# Sheet2.net
KiCad netlist of a schematic drawn in Altium Designer
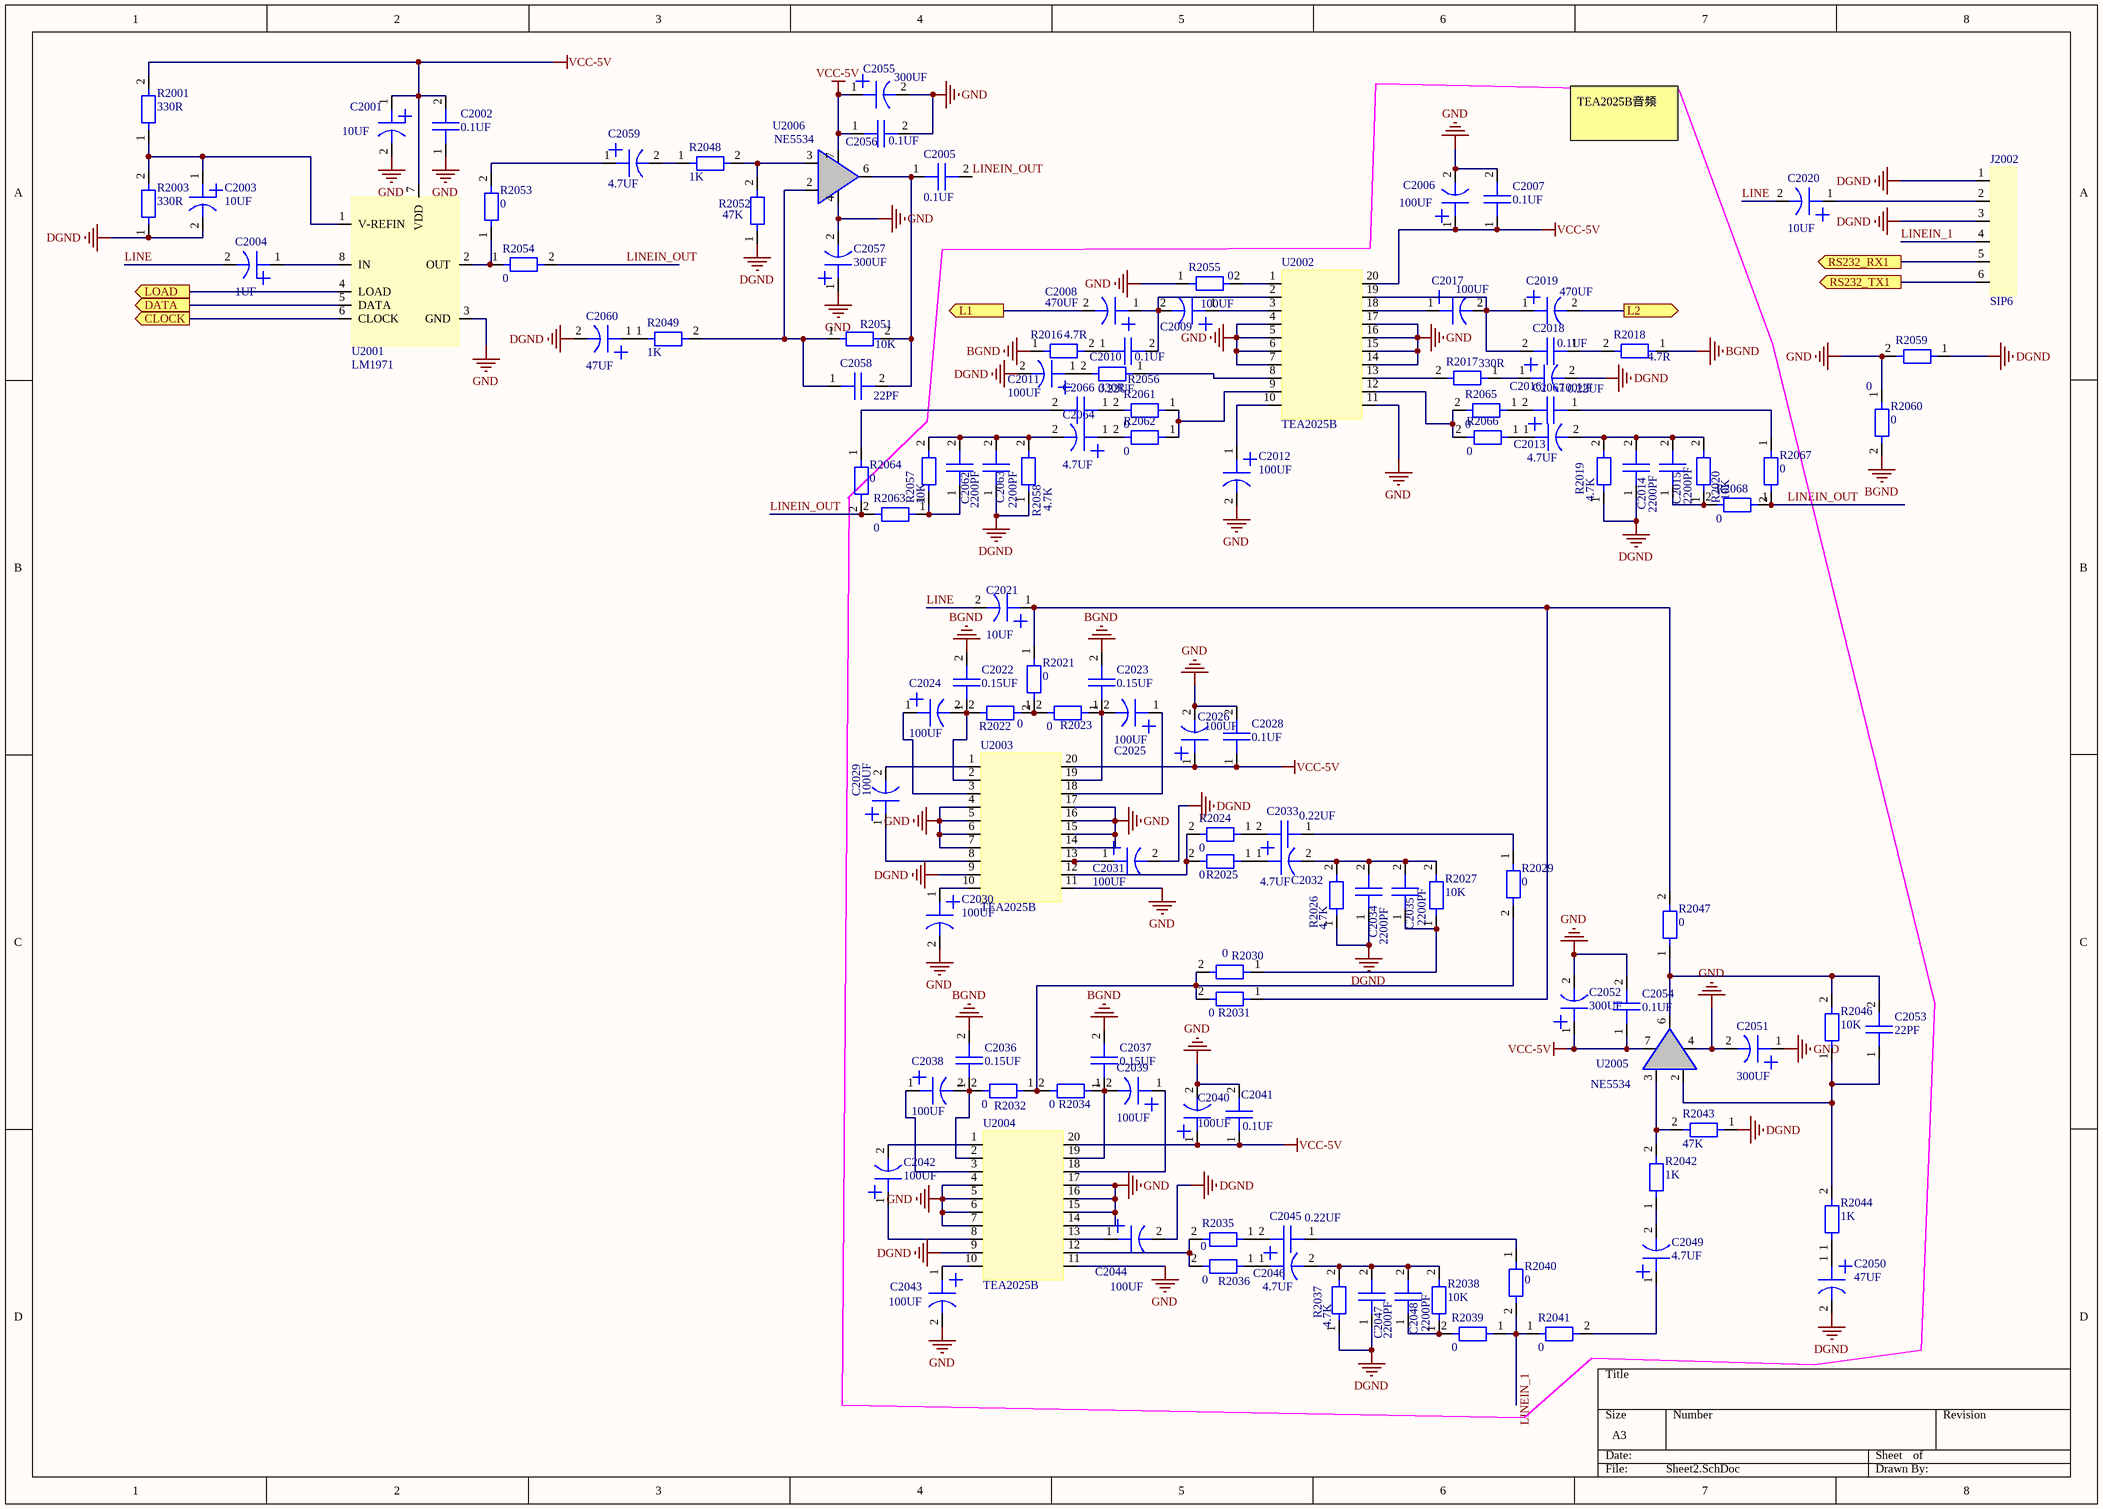
[diagram p0: Sheet2.SchDoc]

(export (version "E")
  (design (tool "Eeschema 10.0.6"))
  (components
    (comp (ref "C2001") (value "10UF") (footprint "7343") (libsource (lib "Schlib1") (part "EC")))
    (comp (ref "C2002") (value "0.1UF") (footprint "0603") (libsource (lib "Schlib1") (part "C")))
    (comp (ref "C2003") (value "10UF") (footprint "7343") (libsource (lib "Schlib1") (part "EC")))
    (comp (ref "C2004") (value "1UF") (footprint "7343") (libsource (lib "Schlib1") (part "EC")))
    (comp (ref "C2005") (value "0.1UF") (footprint "0603") (libsource (lib "Schlib1") (part "C")))
    (comp (ref "C2006") (value "100UF") (footprint "7343") (libsource (lib "Schlib1") (part "JC")))
    (comp (ref "C2007") (value "0.1UF") (footprint "0603") (libsource (lib "Schlib1") (part "C")))
    (comp (ref "C2008") (value "470UF") (footprint "7343") (libsource (lib "Schlib1") (part "JC")))
    (comp (ref "C2009") (value "100UF") (footprint "7343") (libsource (lib "Schlib1") (part "JC")))
    (comp (ref "C2010") (value "0.1UF") (footprint "0603") (libsource (lib "Schlib1") (part "C")))
    (comp (ref "C2011") (value "100UF") (footprint "7343") (libsource (lib "Schlib1") (part "JC")))
    (comp (ref "C2012") (value "100UF") (footprint "7343") (libsource (lib "Schlib1") (part "JC")))
    (comp (ref "C2013") (value "4.7UF") (footprint "7343") (libsource (lib "Schlib1") (part "JC")))
    (comp (ref "C2014") (value "2200PF") (footprint "0603") (libsource (lib "Schlib1") (part "C")))
    (comp (ref "C2015") (value "2200PF") (footprint "0603") (libsource (lib "Schlib1") (part "C")))
    (comp (ref "C2016") (value "100UF") (footprint "7343") (libsource (lib "Schlib1") (part "JC")))
    (comp (ref "C2017") (value "100UF") (footprint "7343") (libsource (lib "Schlib1") (part "JC")))
    (comp (ref "C2018") (value "0.1UF") (footprint "0603") (libsource (lib "Schlib1") (part "C")))
    (comp (ref "C2019") (value "470UF") (footprint "7343") (libsource (lib "Schlib1") (part "JC")))
    (comp (ref "C2020") (value "10UF") (footprint "7343") (libsource (lib "Schlib1") (part "JC")))
    (comp (ref "C2021") (value "10UF") (footprint "7343") (libsource (lib "Schlib1") (part "JC")))
    (comp (ref "C2022") (value "0.15UF") (footprint "0603") (libsource (lib "Schlib1") (part "C")))
    (comp (ref "C2023") (value "0.15UF") (footprint "0603") (libsource (lib "Schlib1") (part "C")))
    (comp (ref "C2024") (value "100UF") (footprint "7343") (libsource (lib "Schlib1") (part "JC")))
    (comp (ref "C2025") (value "100UF") (footprint "7343") (libsource (lib "Schlib1") (part "JC")))
    (comp (ref "C2026") (value "100UF") (footprint "7343") (libsource (lib "Schlib1") (part "JC")))
    (comp (ref "C2028") (value "0.1UF") (footprint "0603") (libsource (lib "Schlib1") (part "C")))
    (comp (ref "C2029") (value "100UF") (footprint "7343") (libsource (lib "Schlib1") (part "JC")))
    (comp (ref "C2030") (value "100UF") (footprint "7343") (libsource (lib "Schlib1") (part "JC")))
    (comp (ref "C2031") (value "100UF") (footprint "7343") (libsource (lib "Schlib1") (part "JC")))
    (comp (ref "C2032") (value "4.7UF") (footprint "7343") (libsource (lib "Schlib1") (part "JC")))
    (comp (ref "C2033") (value "0.22UF") (footprint "0603") (libsource (lib "Schlib1") (part "C")))
    (comp (ref "C2034") (value "2200PF") (footprint "0603") (libsource (lib "Schlib1") (part "C")))
    (comp (ref "C2035") (value "2200PF") (footprint "0603") (libsource (lib "Schlib1") (part "C")))
    (comp (ref "C2036") (value "0.15UF") (footprint "0603") (libsource (lib "Schlib1") (part "C")))
    (comp (ref "C2037") (value "0.15UF") (footprint "0603") (libsource (lib "Schlib1") (part "C")))
    (comp (ref "C2038") (value "100UF") (footprint "7343") (libsource (lib "Schlib1") (part "JC")))
    (comp (ref "C2039") (value "100UF") (footprint "7343") (libsource (lib "Schlib1") (part "JC")))
    (comp (ref "C2040") (value "100UF") (footprint "7343") (libsource (lib "Schlib1") (part "JC")))
    (comp (ref "C2041") (value "0.1UF") (footprint "0603") (libsource (lib "Schlib1") (part "C")))
    (comp (ref "C2042") (value "100UF") (footprint "7343") (libsource (lib "Schlib1") (part "JC")))
    (comp (ref "C2043") (value "100UF") (footprint "7343") (libsource (lib "Schlib1") (part "JC")))
    (comp (ref "C2044") (value "100UF") (footprint "7343") (libsource (lib "Schlib1") (part "JC")))
    (comp (ref "C2045") (value "0.22UF") (footprint "0603") (libsource (lib "Schlib1") (part "C")))
    (comp (ref "C2046") (value "4.7UF") (footprint "7343") (libsource (lib "Schlib1") (part "JC")))
    (comp (ref "C2047") (value "2200PF") (footprint "0603") (libsource (lib "Schlib1") (part "C")))
    (comp (ref "C2048") (value "2200PF") (footprint "0603") (libsource (lib "Schlib1") (part "C")))
    (comp (ref "C2049") (value "4.7UF") (footprint "7343") (libsource (lib "Schlib1") (part "JC")))
    (comp (ref "C2050") (value "47UF") (footprint "7343") (libsource (lib "Schlib1") (part "JC")))
    (comp (ref "C2051") (value "300UF") (footprint "7343") (libsource (lib "Schlib1") (part "JC")))
    (comp (ref "C2052") (value "300UF") (footprint "7343") (libsource (lib "Schlib1") (part "JC")))
    (comp (ref "C2053") (value "22PF") (footprint "0603") (libsource (lib "Schlib1") (part "C")))
    (comp (ref "C2054") (value "0.1UF") (footprint "0603") (libsource (lib "Schlib1") (part "C")))
    (comp (ref "C2055") (value "300UF") (footprint "7343") (libsource (lib "Schlib1") (part "JC")))
    (comp (ref "C2056") (value "0.1UF") (footprint "0603") (libsource (lib "Schlib1") (part "C")))
    (comp (ref "C2057") (value "300UF") (footprint "7343") (libsource (lib "Schlib1") (part "JC")))
    (comp (ref "C2058") (value "22PF") (footprint "0603") (libsource (lib "Schlib1") (part "C")))
    (comp (ref "C2059") (value "4.7UF") (footprint "7343") (libsource (lib "Schlib1") (part "JC")))
    (comp (ref "C2060") (value "47UF") (footprint "7343") (libsource (lib "Schlib1") (part "JC")))
    (comp (ref "C2062") (value "2200PF") (footprint "0603") (libsource (lib "Schlib1") (part "C")))
    (comp (ref "C2063") (value "2200PF") (footprint "0603") (libsource (lib "Schlib1") (part "C")))
    (comp (ref "C2064") (value "4.7UF") (footprint "7343") (libsource (lib "Schlib1") (part "JC")))
    (comp (ref "C2066") (value "0.22UF") (footprint "0603") (libsource (lib "Schlib1") (part "C")))
    (comp (ref "C2067") (value "0.22UF") (footprint "0603") (libsource (lib "Schlib1") (part "C")))
    (comp (ref "J2002") (value "SIP6") (footprint "SIP6") (libsource (lib "Schlib1") (part "SIP6")))
    (comp (ref "R2001") (value "330R") (footprint "0603") (libsource (lib "Schlib1") (part "R")))
    (comp (ref "R2003") (value "330R") (footprint "0603") (libsource (lib "Schlib1") (part "R")))
    (comp (ref "R2016") (value "4.7R") (footprint "0603") (libsource (lib "Schlib1") (part "R")))
    (comp (ref "R2017") (value "330R") (footprint "0603") (libsource (lib "Schlib1") (part "R")))
    (comp (ref "R2018") (value "4.7R") (footprint "0603") (libsource (lib "Schlib1") (part "R")))
    (comp (ref "R2019") (value "4.7K") (footprint "0603") (libsource (lib "Schlib1") (part "R")))
    (comp (ref "R2020") (value "10K") (footprint "0603") (libsource (lib "Schlib1") (part "R")))
    (comp (ref "R2021") (value "0") (footprint "0603") (libsource (lib "Schlib1") (part "R")))
    (comp (ref "R2022") (value "0") (footprint "0603") (libsource (lib "Schlib1") (part "R")))
    (comp (ref "R2023") (value "0") (footprint "0603") (libsource (lib "Schlib1") (part "R")))
    (comp (ref "R2024") (value "0") (footprint "0603") (libsource (lib "Schlib1") (part "R")))
    (comp (ref "R2025") (value "0") (footprint "0603") (libsource (lib "Schlib1") (part "R")))
    (comp (ref "R2026") (value "4.7K") (footprint "0603") (libsource (lib "Schlib1") (part "R")))
    (comp (ref "R2027") (value "10K") (footprint "0603") (libsource (lib "Schlib1") (part "R")))
    (comp (ref "R2029") (value "0") (footprint "0603") (libsource (lib "Schlib1") (part "R")))
    (comp (ref "R2030") (value "0") (footprint "0603") (libsource (lib "Schlib1") (part "R")))
    (comp (ref "R2031") (value "0") (footprint "0603") (libsource (lib "Schlib1") (part "R")))
    (comp (ref "R2032") (value "0") (footprint "0603") (libsource (lib "Schlib1") (part "R")))
    (comp (ref "R2034") (value "0") (footprint "0603") (libsource (lib "Schlib1") (part "R")))
    (comp (ref "R2035") (value "0") (footprint "0603") (libsource (lib "Schlib1") (part "R")))
    (comp (ref "R2036") (value "0") (footprint "0603") (libsource (lib "Schlib1") (part "R")))
    (comp (ref "R2037") (value "4.7K") (footprint "0603") (libsource (lib "Schlib1") (part "R")))
    (comp (ref "R2038") (value "10K") (footprint "0603") (libsource (lib "Schlib1") (part "R")))
    (comp (ref "R2039") (value "0") (footprint "0603") (libsource (lib "Schlib1") (part "R")))
    (comp (ref "R2040") (value "0") (footprint "0603") (libsource (lib "Schlib1") (part "R")))
    (comp (ref "R2041") (value "0") (footprint "0603") (libsource (lib "Schlib1") (part "R")))
    (comp (ref "R2042") (value "1K") (footprint "0603") (libsource (lib "Schlib1") (part "R")))
    (comp (ref "R2043") (value "47K") (footprint "0603") (libsource (lib "Schlib1") (part "R")))
    (comp (ref "R2044") (value "1K") (footprint "0603") (libsource (lib "Schlib1") (part "R")))
    (comp (ref "R2046") (value "10K") (footprint "0603") (libsource (lib "Schlib1") (part "R")))
    (comp (ref "R2047") (value "0") (footprint "0603") (libsource (lib "Schlib1") (part "R")))
    (comp (ref "R2048") (value "1K") (footprint "0603") (libsource (lib "Schlib1") (part "R")))
    (comp (ref "R2049") (value "1K") (footprint "0603") (libsource (lib "Schlib1") (part "R")))
    (comp (ref "R2051") (value "10K") (footprint "0603") (libsource (lib "Schlib1") (part "R")))
    (comp (ref "R2052") (value "47K") (footprint "0603") (libsource (lib "Schlib1") (part "R")))
    (comp (ref "R2053") (value "0") (footprint "0603") (libsource (lib "Schlib1") (part "R")))
    (comp (ref "R2054") (value "0") (footprint "0603") (libsource (lib "Schlib1") (part "R")))
    (comp (ref "R2055") (value "0") (footprint "0603") (libsource (lib "Schlib1") (part "R")))
    (comp (ref "R2056") (value "330R") (footprint "0603") (libsource (lib "Schlib1") (part "R")))
    (comp (ref "R2057") (value "10K") (footprint "0603") (libsource (lib "Schlib1") (part "R")))
    (comp (ref "R2058") (value "4.7K") (footprint "0603") (libsource (lib "Schlib1") (part "R")))
    (comp (ref "R2059") (value "0") (footprint "0603") (libsource (lib "Schlib1") (part "R")))
    (comp (ref "R2060") (value "0") (footprint "0603") (libsource (lib "Schlib1") (part "R")))
    (comp (ref "R2061") (value "0") (footprint "0603") (libsource (lib "Schlib1") (part "R")))
    (comp (ref "R2062") (value "0") (footprint "0603") (libsource (lib "Schlib1") (part "R")))
    (comp (ref "R2063") (value "0") (footprint "0603") (libsource (lib "Schlib1") (part "R")))
    (comp (ref "R2064") (value "0") (footprint "0603") (libsource (lib "Schlib1") (part "R")))
    (comp (ref "R2065") (value "0") (footprint "0603") (libsource (lib "Schlib1") (part "R")))
    (comp (ref "R2066") (value "0") (footprint "0603") (libsource (lib "Schlib1") (part "R")))
    (comp (ref "R2067") (value "0") (footprint "0603") (libsource (lib "Schlib1") (part "R")))
    (comp (ref "R2068") (value "0") (footprint "0603") (libsource (lib "Schlib1") (part "R")))
    (comp (ref "U2001") (value "LM1971") (footprint "TJA1040") (libsource (lib "Schlib1") (part "LM1971")))
    (comp (ref "U2002")
      (value "TEA2025B")
      (footprint "TEA2025B")
      (libsource (lib "Schlib1") (part "TEA2025B"))
    )
    (comp (ref "U2003")
      (value "TEA2025B")
      (footprint "TEA2025B")
      (libsource (lib "Schlib1") (part "TEA2025B"))
    )
    (comp (ref "U2004")
      (value "TEA2025B")
      (footprint "TEA2025B")
      (libsource (lib "Schlib1") (part "TEA2025B"))
    )
    (comp (ref "U2005") (value "NE5534") (footprint "SP2526A") (libsource (lib "Schlib1") (part "NE5534")))
    (comp (ref "U2006") (value "NE5534") (footprint "SP2526A") (libsource (lib "Schlib1") (part "NE5534")))
  )
  (nets
    (net (code "1") (name "/CLOCK") (class "Default")
      (node (ref "U2001") (pin "6") (pinfunction "CLOCK_6") (pintype "passive"))
    )
    (net (code "2") (name "/DATA") (class "Default")
      (node (ref "U2001") (pin "5") (pinfunction "DATA_5") (pintype "passive"))
    )
    (net (code "3") (name "/L1") (class "Default") (node (ref "C2008") (pin "2") (pintype "passive")))
    (net (code "4") (name "/L2") (class "Default") (node (ref "C2019") (pin "2") (pintype "passive")))
    (net (code "5") (name "/LINE") (class "Default")
      (node (ref "C2004") (pin "2") (pintype "passive"))
      (node (ref "C2020") (pin "2") (pintype "passive"))
      (node (ref "C2021") (pin "2") (pintype "passive"))
    )
    (net (code "6") (name "/LINEIN_1") (class "Default")
      (node (ref "J2002") (pin "4") (pintype "passive"))
      (node (ref "R2039") (pin "1") (pintype "passive"))
      (node (ref "R2040") (pin "2") (pintype "passive"))
      (node (ref "R2041") (pin "1") (pintype "passive"))
    )
    (net (code "7") (name "/LINEIN_OUT") (class "Default")
      (node (ref "C2005") (pin "2") (pintype "passive"))
      (node (ref "R2054") (pin "2") (pintype "passive"))
      (node (ref "R2063") (pin "2") (pintype "passive"))
      (node (ref "R2064") (pin "2") (pintype "passive"))
      (node (ref "R2067") (pin "2") (pintype "passive"))
      (node (ref "R2068") (pin "1") (pintype "passive"))
    )
    (net (code "8") (name "/LOAD") (class "Default")
      (node (ref "U2001") (pin "4") (pinfunction "LOAD_4") (pintype "passive"))
    )
    (net (code "9") (name "/RS232_RX1") (class "Default") (node (ref "J2002") (pin "5") (pintype "passive")))
    (net (code "10") (name "/RS232_TX1") (class "Default") (node (ref "J2002") (pin "6") (pintype "passive")))
    (net (code "11") (name "BGND") (class "Default")
      (node (ref "C2022") (pin "2") (pintype "passive"))
      (node (ref "C2023") (pin "2") (pintype "passive"))
      (node (ref "C2036") (pin "2") (pintype "passive"))
      (node (ref "C2037") (pin "2") (pintype "passive"))
      (node (ref "R2016") (pin "1") (pintype "passive"))
      (node (ref "R2018") (pin "1") (pintype "passive"))
      (node (ref "R2060") (pin "2") (pintype "passive"))
    )
    (net (code "12") (name "DGND") (class "Default")
      (node (ref "C2003") (pin "2") (pintype "passive"))
      (node (ref "C2011") (pin "2") (pintype "passive"))
      (node (ref "C2014") (pin "1") (pintype "passive"))
      (node (ref "C2016") (pin "2") (pintype "passive"))
      (node (ref "C2031") (pin "2") (pintype "passive"))
      (node (ref "C2034") (pin "1") (pintype "passive"))
      (node (ref "C2044") (pin "2") (pintype "passive"))
      (node (ref "C2047") (pin "1") (pintype "passive"))
      (node (ref "C2050") (pin "2") (pintype "passive"))
      (node (ref "C2060") (pin "2") (pintype "passive"))
      (node (ref "C2063") (pin "1") (pintype "passive"))
      (node (ref "J2002") (pin "1") (pintype "passive"))
      (node (ref "J2002") (pin "3") (pintype "passive"))
      (node (ref "R2003") (pin "1") (pintype "passive"))
      (node (ref "R2019") (pin "1") (pintype "passive"))
      (node (ref "R2026") (pin "1") (pintype "passive"))
      (node (ref "R2037") (pin "1") (pintype "passive"))
      (node (ref "R2043") (pin "1") (pintype "passive"))
      (node (ref "R2052") (pin "1") (pintype "passive"))
      (node (ref "R2058") (pin "1") (pintype "passive"))
      (node (ref "R2059") (pin "1") (pintype "passive"))
      (node (ref "U2003") (pin "9") (pintype "passive"))
      (node (ref "U2004") (pin "9") (pintype "passive"))
    )
    (net (code "13") (name "GND") (class "Default")
      (node (ref "C2001") (pin "2") (pintype "passive"))
      (node (ref "C2002") (pin "1") (pintype "passive"))
      (node (ref "C2006") (pin "2") (pintype "passive"))
      (node (ref "C2007") (pin "2") (pintype "passive"))
      (node (ref "C2012") (pin "2") (pintype "passive"))
      (node (ref "C2026") (pin "2") (pintype "passive"))
      (node (ref "C2028") (pin "2") (pintype "passive"))
      (node (ref "C2030") (pin "2") (pintype "passive"))
      (node (ref "C2040") (pin "2") (pintype "passive"))
      (node (ref "C2041") (pin "2") (pintype "passive"))
      (node (ref "C2043") (pin "2") (pintype "passive"))
      (node (ref "C2051") (pin "1") (pintype "passive"))
      (node (ref "C2051") (pin "2") (pintype "passive"))
      (node (ref "C2052") (pin "2") (pintype "passive"))
      (node (ref "C2054") (pin "2") (pintype "passive"))
      (node (ref "C2055") (pin "2") (pintype "passive"))
      (node (ref "C2056") (pin "2") (pintype "passive"))
      (node (ref "C2057") (pin "1") (pintype "passive"))
      (node (ref "C2057") (pin "2") (pintype "passive"))
      (node (ref "R2055") (pin "1") (pintype "passive"))
      (node (ref "R2059") (pin "2") (pintype "passive"))
      (node (ref "R2060") (pin "1") (pintype "passive"))
      (node (ref "U2001") (pin "3") (pinfunction "GND_3") (pintype "passive"))
      (node (ref "U2002") (pin "11") (pintype "passive"))
      (node (ref "U2002") (pin "14") (pintype "passive"))
      (node (ref "U2002") (pin "15") (pintype "passive"))
      (node (ref "U2002") (pin "16") (pintype "passive"))
      (node (ref "U2002") (pin "17") (pintype "passive"))
      (node (ref "U2002") (pin "4") (pintype "passive"))
      (node (ref "U2002") (pin "5") (pintype "passive"))
      (node (ref "U2002") (pin "6") (pintype "passive"))
      (node (ref "U2002") (pin "7") (pintype "passive"))
      (node (ref "U2003") (pin "11") (pintype "passive"))
      (node (ref "U2003") (pin "14") (pintype "passive"))
      (node (ref "U2003") (pin "15") (pintype "passive"))
      (node (ref "U2003") (pin "16") (pintype "passive"))
      (node (ref "U2003") (pin "17") (pintype "passive"))
      (node (ref "U2003") (pin "4") (pintype "passive"))
      (node (ref "U2003") (pin "5") (pintype "passive"))
      (node (ref "U2003") (pin "6") (pintype "passive"))
      (node (ref "U2003") (pin "7") (pintype "passive"))
      (node (ref "U2004") (pin "11") (pintype "passive"))
      (node (ref "U2004") (pin "14") (pintype "passive"))
      (node (ref "U2004") (pin "15") (pintype "passive"))
      (node (ref "U2004") (pin "16") (pintype "passive"))
      (node (ref "U2004") (pin "17") (pintype "passive"))
      (node (ref "U2004") (pin "4") (pintype "passive"))
      (node (ref "U2004") (pin "5") (pintype "passive"))
      (node (ref "U2004") (pin "6") (pintype "passive"))
      (node (ref "U2004") (pin "7") (pintype "passive"))
      (node (ref "U2005") (pin "4") (pintype "passive"))
      (node (ref "U2006") (pin "4") (pintype "passive"))
    )
    (net (code "14") (name "Net-(C2005-Pad1)") (class "Default")
      (node (ref "C2005") (pin "1") (pintype "passive"))
      (node (ref "C2058") (pin "2") (pintype "passive"))
      (node (ref "R2051") (pin "2") (pintype "passive"))
      (node (ref "U2006") (pin "6") (pintype "passive"))
    )
    (net (code "15") (name "Net-(C2008-Pad1)") (class "Default")
      (node (ref "C2008") (pin "1") (pintype "passive"))
      (node (ref "C2009") (pin "2") (pintype "passive"))
      (node (ref "C2010") (pin "2") (pintype "passive"))
      (node (ref "U2002") (pin "2") (pintype "passive"))
    )
    (net (code "16") (name "Net-(C2009-Pad1)") (class "Default")
      (node (ref "C2009") (pin "1") (pintype "passive"))
      (node (ref "U2002") (pin "3") (pintype "passive"))
    )
    (net (code "17") (name "Net-(C2010-Pad1)") (class "Default")
      (node (ref "C2010") (pin "1") (pintype "passive"))
      (node (ref "R2016") (pin "2") (pintype "passive"))
    )
    (net (code "18") (name "Net-(C2011-Pad1)") (class "Default")
      (node (ref "C2011") (pin "1") (pintype "passive"))
      (node (ref "R2056") (pin "2") (pintype "passive"))
    )
    (net (code "19") (name "Net-(C2012-Pad1)") (class "Default")
      (node (ref "C2012") (pin "1") (pintype "passive"))
      (node (ref "U2002") (pin "10") (pintype "passive"))
    )
    (net (code "20") (name "Net-(C2013-Pad1)") (class "Default")
      (node (ref "C2013") (pin "1") (pintype "passive"))
      (node (ref "R2066") (pin "1") (pintype "passive"))
    )
    (net (code "21") (name "Net-(C2013-Pad2)") (class "Default")
      (node (ref "C2013") (pin "2") (pintype "passive"))
      (node (ref "C2014") (pin "2") (pintype "passive"))
      (node (ref "C2015") (pin "2") (pintype "passive"))
      (node (ref "R2019") (pin "2") (pintype "passive"))
      (node (ref "R2020") (pin "2") (pintype "passive"))
    )
    (net (code "22") (name "Net-(C2015-Pad1)") (class "Default")
      (node (ref "C2015") (pin "1") (pintype "passive"))
      (node (ref "R2020") (pin "1") (pintype "passive"))
      (node (ref "R2068") (pin "2") (pintype "passive"))
    )
    (net (code "23") (name "Net-(C2016-Pad1)") (class "Default")
      (node (ref "C2016") (pin "1") (pintype "passive"))
      (node (ref "R2017") (pin "1") (pintype "passive"))
    )
    (net (code "24") (name "Net-(C2017-Pad1)") (class "Default")
      (node (ref "C2017") (pin "1") (pintype "passive"))
      (node (ref "U2002") (pin "18") (pintype "passive"))
    )
    (net (code "25") (name "Net-(C2017-Pad2)") (class "Default")
      (node (ref "C2017") (pin "2") (pintype "passive"))
      (node (ref "C2018") (pin "2") (pintype "passive"))
      (node (ref "C2019") (pin "1") (pintype "passive"))
      (node (ref "U2002") (pin "19") (pintype "passive"))
    )
    (net (code "26") (name "Net-(C2018-Pad1)") (class "Default")
      (node (ref "C2018") (pin "1") (pintype "passive"))
      (node (ref "R2018") (pin "2") (pintype "passive"))
    )
    (net (code "27") (name "Net-(C2020-Pad1)") (class "Default")
      (node (ref "C2020") (pin "1") (pintype "passive"))
      (node (ref "J2002") (pin "2") (pintype "passive"))
    )
    (net (code "28") (name "Net-(C2021-Pad1)") (class "Default")
      (node (ref "C2021") (pin "1") (pintype "passive"))
      (node (ref "R2021") (pin "1") (pintype "passive"))
      (node (ref "R2031") (pin "1") (pintype "passive"))
      (node (ref "R2047") (pin "2") (pintype "passive"))
    )
    (net (code "29") (name "Net-(C2022-Pad1)") (class "Default")
      (node (ref "C2022") (pin "1") (pintype "passive"))
      (node (ref "C2024") (pin "2") (pintype "passive"))
      (node (ref "R2022") (pin "2") (pintype "passive"))
      (node (ref "U2003") (pin "2") (pintype "passive"))
    )
    (net (code "30") (name "Net-(C2023-Pad1)") (class "Default")
      (node (ref "C2023") (pin "1") (pintype "passive"))
      (node (ref "C2025") (pin "2") (pintype "passive"))
      (node (ref "R2023") (pin "1") (pintype "passive"))
      (node (ref "U2003") (pin "19") (pintype "passive"))
    )
    (net (code "31") (name "Net-(C2024-Pad1)") (class "Default")
      (node (ref "C2024") (pin "1") (pintype "passive"))
      (node (ref "U2003") (pin "3") (pintype "passive"))
    )
    (net (code "32") (name "Net-(C2025-Pad1)") (class "Default")
      (node (ref "C2025") (pin "1") (pintype "passive"))
      (node (ref "U2003") (pin "18") (pintype "passive"))
    )
    (net (code "33") (name "Net-(C2029-Pad1)") (class "Default")
      (node (ref "C2029") (pin "1") (pintype "passive"))
      (node (ref "U2003") (pin "8") (pintype "passive"))
    )
    (net (code "34") (name "Net-(C2029-Pad2)") (class "Default")
      (node (ref "C2029") (pin "2") (pintype "passive"))
      (node (ref "U2003") (pin "1") (pintype "passive"))
    )
    (net (code "35") (name "Net-(C2030-Pad1)") (class "Default")
      (node (ref "C2030") (pin "1") (pintype "passive"))
      (node (ref "U2003") (pin "10") (pintype "passive"))
    )
    (net (code "36") (name "Net-(C2031-Pad1)") (class "Default")
      (node (ref "C2031") (pin "1") (pintype "passive"))
      (node (ref "U2003") (pin "13") (pintype "passive"))
    )
    (net (code "37") (name "Net-(C2032-Pad1)") (class "Default")
      (node (ref "C2032") (pin "1") (pintype "passive"))
      (node (ref "R2025") (pin "1") (pintype "passive"))
    )
    (net (code "38") (name "Net-(C2032-Pad2)") (class "Default")
      (node (ref "C2032") (pin "2") (pintype "passive"))
      (node (ref "C2034") (pin "2") (pintype "passive"))
      (node (ref "C2035") (pin "2") (pintype "passive"))
      (node (ref "R2026") (pin "2") (pintype "passive"))
      (node (ref "R2027") (pin "2") (pintype "passive"))
    )
    (net (code "39") (name "Net-(C2033-Pad1)") (class "Default")
      (node (ref "C2033") (pin "1") (pintype "passive"))
      (node (ref "R2029") (pin "1") (pintype "passive"))
    )
    (net (code "40") (name "Net-(C2033-Pad2)") (class "Default")
      (node (ref "C2033") (pin "2") (pintype "passive"))
      (node (ref "R2024") (pin "1") (pintype "passive"))
    )
    (net (code "41") (name "Net-(C2035-Pad1)") (class "Default")
      (node (ref "C2035") (pin "1") (pintype "passive"))
      (node (ref "R2027") (pin "1") (pintype "passive"))
      (node (ref "R2030") (pin "1") (pintype "passive"))
    )
    (net (code "42") (name "Net-(C2036-Pad1)") (class "Default")
      (node (ref "C2036") (pin "1") (pintype "passive"))
      (node (ref "C2038") (pin "2") (pintype "passive"))
      (node (ref "R2032") (pin "2") (pintype "passive"))
      (node (ref "U2004") (pin "2") (pintype "passive"))
    )
    (net (code "43") (name "Net-(C2037-Pad1)") (class "Default")
      (node (ref "C2037") (pin "1") (pintype "passive"))
      (node (ref "C2039") (pin "2") (pintype "passive"))
      (node (ref "R2034") (pin "1") (pintype "passive"))
      (node (ref "U2004") (pin "19") (pintype "passive"))
    )
    (net (code "44") (name "Net-(C2038-Pad1)") (class "Default")
      (node (ref "C2038") (pin "1") (pintype "passive"))
      (node (ref "U2004") (pin "3") (pintype "passive"))
    )
    (net (code "45") (name "Net-(C2039-Pad1)") (class "Default")
      (node (ref "C2039") (pin "1") (pintype "passive"))
      (node (ref "U2004") (pin "18") (pintype "passive"))
    )
    (net (code "46") (name "Net-(C2042-Pad1)") (class "Default")
      (node (ref "C2042") (pin "1") (pintype "passive"))
      (node (ref "U2004") (pin "8") (pintype "passive"))
    )
    (net (code "47") (name "Net-(C2042-Pad2)") (class "Default")
      (node (ref "C2042") (pin "2") (pintype "passive"))
      (node (ref "U2004") (pin "1") (pintype "passive"))
    )
    (net (code "48") (name "Net-(C2043-Pad1)") (class "Default")
      (node (ref "C2043") (pin "1") (pintype "passive"))
      (node (ref "U2004") (pin "10") (pintype "passive"))
    )
    (net (code "49") (name "Net-(C2044-Pad1)") (class "Default")
      (node (ref "C2044") (pin "1") (pintype "passive"))
      (node (ref "U2004") (pin "13") (pintype "passive"))
    )
    (net (code "50") (name "Net-(C2045-Pad1)") (class "Default")
      (node (ref "C2045") (pin "1") (pintype "passive"))
      (node (ref "R2040") (pin "1") (pintype "passive"))
    )
    (net (code "51") (name "Net-(C2045-Pad2)") (class "Default")
      (node (ref "C2045") (pin "2") (pintype "passive"))
      (node (ref "R2035") (pin "1") (pintype "passive"))
    )
    (net (code "52") (name "Net-(C2046-Pad1)") (class "Default")
      (node (ref "C2046") (pin "1") (pintype "passive"))
      (node (ref "R2036") (pin "1") (pintype "passive"))
    )
    (net (code "53") (name "Net-(C2046-Pad2)") (class "Default")
      (node (ref "C2046") (pin "2") (pintype "passive"))
      (node (ref "C2047") (pin "2") (pintype "passive"))
      (node (ref "C2048") (pin "2") (pintype "passive"))
      (node (ref "R2037") (pin "2") (pintype "passive"))
      (node (ref "R2038") (pin "2") (pintype "passive"))
    )
    (net (code "54") (name "Net-(C2048-Pad1)") (class "Default")
      (node (ref "C2048") (pin "1") (pintype "passive"))
      (node (ref "R2038") (pin "1") (pintype "passive"))
      (node (ref "R2039") (pin "2") (pintype "passive"))
    )
    (net (code "55") (name "Net-(C2049-Pad1)") (class "Default")
      (node (ref "C2049") (pin "1") (pintype "passive"))
      (node (ref "R2041") (pin "2") (pintype "passive"))
    )
    (net (code "56") (name "Net-(C2049-Pad2)") (class "Default")
      (node (ref "C2049") (pin "2") (pintype "passive"))
      (node (ref "R2042") (pin "1") (pintype "passive"))
    )
    (net (code "57") (name "Net-(C2050-Pad1)") (class "Default")
      (node (ref "C2050") (pin "1") (pintype "passive"))
      (node (ref "R2044") (pin "1") (pintype "passive"))
    )
    (net (code "58") (name "Net-(C2053-Pad1)") (class "Default")
      (node (ref "C2053") (pin "1") (pintype "passive"))
      (node (ref "R2044") (pin "2") (pintype "passive"))
      (node (ref "R2046") (pin "1") (pintype "passive"))
      (node (ref "U2005") (pin "2") (pintype "passive"))
    )
    (net (code "59") (name "Net-(C2053-Pad2)") (class "Default")
      (node (ref "C2053") (pin "2") (pintype "passive"))
      (node (ref "R2046") (pin "2") (pintype "passive"))
      (node (ref "R2047") (pin "1") (pintype "passive"))
      (node (ref "U2005") (pin "6") (pintype "passive"))
    )
    (net (code "60") (name "Net-(C2058-Pad1)") (class "Default")
      (node (ref "C2058") (pin "1") (pintype "passive"))
      (node (ref "R2049") (pin "2") (pintype "passive"))
      (node (ref "R2051") (pin "1") (pintype "passive"))
      (node (ref "U2006") (pin "2") (pintype "passive"))
    )
    (net (code "61") (name "Net-(C2059-Pad1)") (class "Default")
      (node (ref "C2059") (pin "1") (pintype "passive"))
      (node (ref "R2053") (pin "2") (pintype "passive"))
    )
    (net (code "62") (name "Net-(C2059-Pad2)") (class "Default")
      (node (ref "C2059") (pin "2") (pintype "passive"))
      (node (ref "R2048") (pin "1") (pintype "passive"))
    )
    (net (code "63") (name "Net-(C2060-Pad1)") (class "Default")
      (node (ref "C2060") (pin "1") (pintype "passive"))
      (node (ref "R2049") (pin "1") (pintype "passive"))
    )
    (net (code "64") (name "Net-(C2062-Pad1)") (class "Default")
      (node (ref "C2062") (pin "1") (pintype "passive"))
      (node (ref "R2057") (pin "1") (pintype "passive"))
      (node (ref "R2063") (pin "1") (pintype "passive"))
    )
    (net (code "65") (name "Net-(C2062-Pad2)") (class "Default")
      (node (ref "C2062") (pin "2") (pintype "passive"))
      (node (ref "C2063") (pin "2") (pintype "passive"))
      (node (ref "C2064") (pin "2") (pintype "passive"))
      (node (ref "R2057") (pin "2") (pintype "passive"))
      (node (ref "R2058") (pin "2") (pintype "passive"))
    )
    (net (code "66") (name "Net-(C2064-Pad1)") (class "Default")
      (node (ref "C2064") (pin "1") (pintype "passive"))
      (node (ref "R2062") (pin "2") (pintype "passive"))
    )
    (net (code "67") (name "Net-(C2066-Pad1)") (class "Default")
      (node (ref "C2066") (pin "1") (pintype "passive"))
      (node (ref "R2061") (pin "2") (pintype "passive"))
    )
    (net (code "68") (name "Net-(C2066-Pad2)") (class "Default")
      (node (ref "C2066") (pin "2") (pintype "passive"))
      (node (ref "R2064") (pin "1") (pintype "passive"))
    )
    (net (code "69") (name "Net-(C2067-Pad1)") (class "Default")
      (node (ref "C2067") (pin "1") (pintype "passive"))
      (node (ref "R2067") (pin "1") (pintype "passive"))
    )
    (net (code "70") (name "Net-(C2067-Pad2)") (class "Default")
      (node (ref "C2067") (pin "2") (pintype "passive"))
      (node (ref "R2065") (pin "1") (pintype "passive"))
    )
    (net (code "71") (name "Net-(R2017-Pad2)") (class "Default")
      (node (ref "R2017") (pin "2") (pintype "passive"))
      (node (ref "U2002") (pin "13") (pintype "passive"))
    )
    (net (code "72") (name "Net-(R2021-Pad2)") (class "Default")
      (node (ref "R2021") (pin "2") (pintype "passive"))
      (node (ref "R2022") (pin "1") (pintype "passive"))
      (node (ref "R2023") (pin "2") (pintype "passive"))
    )
    (net (code "73") (name "Net-(R2024-Pad2)") (class "Default")
      (node (ref "R2024") (pin "2") (pintype "passive"))
      (node (ref "R2025") (pin "2") (pintype "passive"))
      (node (ref "U2003") (pin "12") (pintype "passive"))
    )
    (net (code "74") (name "Net-(R2029-Pad2)") (class "Default")
      (node (ref "R2029") (pin "2") (pintype "passive"))
      (node (ref "R2030") (pin "2") (pintype "passive"))
      (node (ref "R2031") (pin "2") (pintype "passive"))
      (node (ref "R2032") (pin "1") (pintype "passive"))
      (node (ref "R2034") (pin "2") (pintype "passive"))
    )
    (net (code "75") (name "Net-(R2035-Pad2)") (class "Default")
      (node (ref "R2035") (pin "2") (pintype "passive"))
      (node (ref "R2036") (pin "2") (pintype "passive"))
      (node (ref "U2004") (pin "12") (pintype "passive"))
    )
    (net (code "76") (name "Net-(R2042-Pad2)") (class "Default")
      (node (ref "R2042") (pin "2") (pintype "passive"))
      (node (ref "R2043") (pin "2") (pintype "passive"))
      (node (ref "U2005") (pin "3") (pintype "passive"))
    )
    (net (code "77") (name "Net-(R2048-Pad2)") (class "Default")
      (node (ref "R2048") (pin "2") (pintype "passive"))
      (node (ref "R2052") (pin "2") (pintype "passive"))
      (node (ref "U2006") (pin "3") (pintype "passive"))
    )
    (net (code "78") (name "Net-(R2055-Pad2)") (class "Default")
      (node (ref "R2055") (pin "2") (pintype "passive"))
      (node (ref "U2002") (pin "1") (pintype "passive"))
    )
    (net (code "79") (name "Net-(R2056-Pad1)") (class "Default")
      (node (ref "R2056") (pin "1") (pintype "passive"))
      (node (ref "U2002") (pin "8") (pintype "passive"))
    )
    (net (code "80") (name "Net-(R2061-Pad1)") (class "Default")
      (node (ref "R2061") (pin "1") (pintype "passive"))
      (node (ref "R2062") (pin "1") (pintype "passive"))
      (node (ref "U2002") (pin "9") (pintype "passive"))
    )
    (net (code "81") (name "Net-(R2065-Pad2)") (class "Default")
      (node (ref "R2065") (pin "2") (pintype "passive"))
      (node (ref "R2066") (pin "2") (pintype "passive"))
      (node (ref "U2002") (pin "12") (pintype "passive"))
    )
    (net (code "82") (name "Net-(U2001-IN)") (class "Default")
      (node (ref "C2004") (pin "1") (pintype "passive"))
      (node (ref "U2001") (pin "8") (pinfunction "IN_8") (pintype "passive"))
    )
    (net (code "83") (name "Net-(U2001-OUT)") (class "Default")
      (node (ref "R2053") (pin "1") (pintype "passive"))
      (node (ref "R2054") (pin "1") (pintype "passive"))
      (node (ref "U2001") (pin "2") (pinfunction "OUT_2") (pintype "passive"))
    )
    (net (code "84") (name "Net-(U2001-V-REFIN)") (class "Default")
      (node (ref "C2003") (pin "1") (pintype "passive"))
      (node (ref "R2001") (pin "1") (pintype "passive"))
      (node (ref "R2003") (pin "2") (pintype "passive"))
      (node (ref "U2001") (pin "1") (pinfunction "V-REFIN_1") (pintype "passive"))
    )
    (net (code "85") (name "VCC-5V") (class "Default")
      (node (ref "C2001") (pin "1") (pintype "passive"))
      (node (ref "C2002") (pin "2") (pintype "passive"))
      (node (ref "C2006") (pin "1") (pintype "passive"))
      (node (ref "C2007") (pin "1") (pintype "passive"))
      (node (ref "C2026") (pin "1") (pintype "passive"))
      (node (ref "C2028") (pin "1") (pintype "passive"))
      (node (ref "C2040") (pin "1") (pintype "passive"))
      (node (ref "C2041") (pin "1") (pintype "passive"))
      (node (ref "C2052") (pin "1") (pintype "passive"))
      (node (ref "C2054") (pin "1") (pintype "passive"))
      (node (ref "C2055") (pin "1") (pintype "passive"))
      (node (ref "C2056") (pin "1") (pintype "passive"))
      (node (ref "R2001") (pin "2") (pintype "passive"))
      (node (ref "U2001") (pin "7") (pinfunction "VDD_7") (pintype "passive"))
      (node (ref "U2002") (pin "20") (pintype "passive"))
      (node (ref "U2003") (pin "20") (pintype "passive"))
      (node (ref "U2004") (pin "20") (pintype "passive"))
      (node (ref "U2005") (pin "7") (pintype "passive"))
      (node (ref "U2006") (pin "7") (pintype "passive"))
    )
  )
)
